# Blinky.net
KiCad netlist of a schematic drawn in Altium Designer
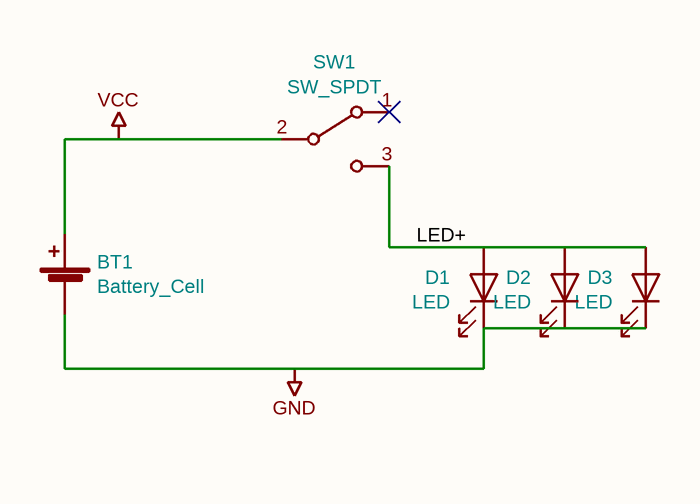
[diagram p0: Blinky.SchDoc]

(export (version "E")
  (design (tool "Eeschema 10.0.6"))
  (components
    (comp (ref "BT1") (value "Battery_Cell") (libsource (lib "Device") (part "Battery_Cell")))
    (comp (ref "D1") (value "LED") (libsource (lib "Device") (part "LED")))
    (comp (ref "D2") (value "LED") (libsource (lib "Device") (part "LED")))
    (comp (ref "D3") (value "LED") (libsource (lib "Device") (part "LED")))
    (comp (ref "SW1") (value "SW_SPDT") (libsource (lib "Switch") (part "SW_SPDT")))
  )
  (nets
    (net (code "1") (name "/LED+") (class "Default")
      (node (ref "D1") (pin "2") (pinfunction "A_2") (pintype "passive"))
      (node (ref "D2") (pin "2") (pinfunction "A_2") (pintype "passive"))
      (node (ref "D3") (pin "2") (pinfunction "A_2") (pintype "passive"))
      (node (ref "SW1") (pin "3") (pinfunction "C_3") (pintype "passive"))
    )
    (net (code "2") (name "GND") (class "Default")
      (node (ref "BT1") (pin "2") (pinfunction "-_2") (pintype "passive"))
      (node (ref "D1") (pin "1") (pinfunction "K_1") (pintype "passive"))
      (node (ref "D2") (pin "1") (pinfunction "K_1") (pintype "passive"))
      (node (ref "D3") (pin "1") (pinfunction "K_1") (pintype "passive"))
    )
    (net (code "3") (name "VCC") (class "Default")
      (node (ref "BT1") (pin "1") (pinfunction "+_1") (pintype "passive"))
      (node (ref "SW1") (pin "2") (pinfunction "B_2") (pintype "passive"))
    )
    (net (code "4") (name "unconnected-(SW1-A-Pad1)") (class "Default")
      (node (ref "SW1") (pin "1") (pinfunction "A_1") (pintype "passive+no_connect"))
    )
  )
)
